# Circuit_diagram_source_file.net
KiCad netlist of a schematic drawn in Altium Designer
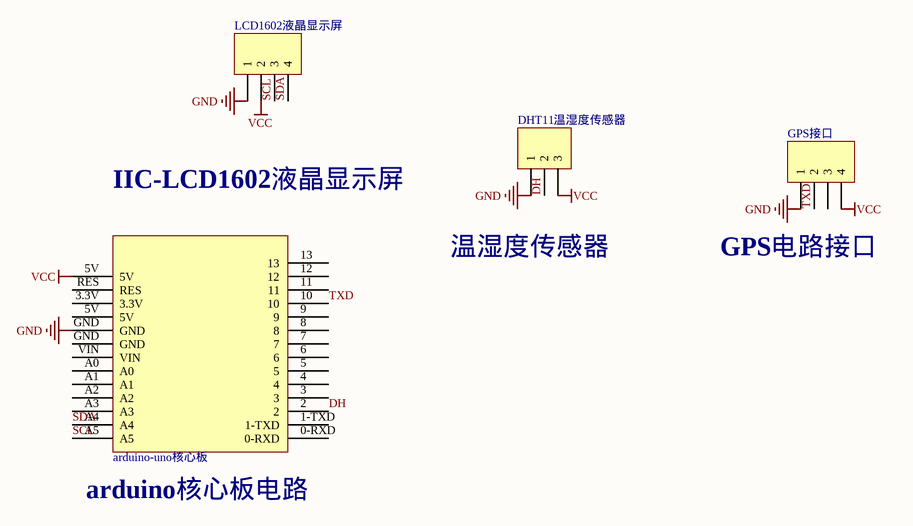
[diagram p0: Circuit diagram source file.SchDoc]

(export (version "E")
  (design (tool "Eeschema 10.0.6"))
  (components
    (comp (ref "arduino-uno核心板") (value "Component_2") (libsource (lib "Schlib1") (part "Component_2")))
    (comp (ref "DHT11温湿度传感器")
      (value "Header 3")
      (footprint "HDR1X3")
      (description "Header, 3-Pin")
      (fields (field (name "PUBLISHER") "Altium Limited"))
      (libsource (lib "Miscellaneous Connectors") (part "Header 3"))
    )
    (comp (ref "GPS接口")
      (value "Header 4")
      (footprint "HDR1X4")
      (description "Header, 4-Pin")
      (fields (field (name "PUBLISHER") "Altium Limited"))
      (libsource (lib "Miscellaneous Connectors") (part "Header 4"))
    )
    (comp (ref "LCD1602液晶显示屏")
      (value "Header 4")
      (footprint "HDR1X4")
      (description "Header, 4-Pin")
      (fields (field (name "PUBLISHER") "Altium Limited"))
      (libsource (lib "Miscellaneous Connectors") (part "Header 4"))
    )
  )
  (nets
    (net (code "1") (name "/DH") (class "Default")
      (node (ref "DHT11温湿度传感器") (pin "2") (pinfunction "2_2") (pintype "passive"))
      (node (ref "arduino-uno核心板") (pin "2") (pinfunction "2_2") (pintype "passive"))
    )
    (net (code "2") (name "/SCL") (class "Default")
      (node (ref "LCD1602液晶显示屏") (pin "3") (pinfunction "3_3") (pintype "passive"))
      (node (ref "arduino-uno核心板") (pin "A5") (pinfunction "A5_A5") (pintype "passive"))
    )
    (net (code "3") (name "/SDA") (class "Default")
      (node (ref "LCD1602液晶显示屏") (pin "4") (pinfunction "4_4") (pintype "passive"))
      (node (ref "arduino-uno核心板") (pin "A4") (pinfunction "A4_A4") (pintype "passive"))
    )
    (net (code "4") (name "/TXD") (class "Default")
      (node (ref "GPS接口") (pin "2") (pinfunction "2_2") (pintype "passive"))
      (node (ref "arduino-uno核心板") (pin "10") (pinfunction "10_10") (pintype "passive"))
    )
    (net (code "5") (name "GND") (class "Default")
      (node (ref "DHT11温湿度传感器") (pin "1") (pinfunction "1_1") (pintype "passive"))
      (node (ref "GPS接口") (pin "1") (pinfunction "1_1") (pintype "passive"))
      (node (ref "LCD1602液晶显示屏") (pin "1") (pinfunction "1_1") (pintype "passive"))
      (node (ref "arduino-uno核心板") (pin "GND") (pinfunction "GND_GND") (pintype "passive"))
    )
    (net (code "6") (name "VCC") (class "Default")
      (node (ref "DHT11温湿度传感器") (pin "3") (pinfunction "3_3") (pintype "passive"))
      (node (ref "GPS接口") (pin "4") (pinfunction "4_4") (pintype "passive"))
      (node (ref "LCD1602液晶显示屏") (pin "2") (pinfunction "2_2") (pintype "passive"))
      (node (ref "arduino-uno核心板") (pin "5V") (pinfunction "5V_5V") (pintype "passive"))
    )
    (net (code "7") (name "unconnected-(GPS接口-Pad3)") (class "Default")
      (node (ref "GPS接口") (pin "3") (pinfunction "3_3") (pintype "passive"))
    )
    (net (code "8") (name "unconnected-(arduino-uno核心板-Pad0-RXD)") (class "Default")
      (node (ref "arduino-uno核心板") (pin "0-RXD") (pinfunction "0-RXD_0-RXD") (pintype "passive"))
    )
    (net (code "9") (name "unconnected-(arduino-uno核心板-Pad1-TXD)") (class "Default")
      (node (ref "arduino-uno核心板") (pin "1-TXD") (pinfunction "1-TXD_1-TXD") (pintype "passive"))
    )
    (net (code "10") (name "unconnected-(arduino-uno核心板-Pad3)") (class "Default")
      (node (ref "arduino-uno核心板") (pin "3") (pinfunction "3_3") (pintype "passive"))
    )
    (net (code "11") (name "unconnected-(arduino-uno核心板-Pad3.3V)") (class "Default")
      (node (ref "arduino-uno核心板") (pin "3.3V") (pinfunction "3.3V_3.3V") (pintype "passive"))
    )
    (net (code "12") (name "unconnected-(arduino-uno核心板-Pad4)") (class "Default")
      (node (ref "arduino-uno核心板") (pin "4") (pinfunction "4_4") (pintype "passive"))
    )
    (net (code "13") (name "unconnected-(arduino-uno核心板-Pad5)") (class "Default")
      (node (ref "arduino-uno核心板") (pin "5") (pinfunction "5_5") (pintype "passive"))
    )
    (net (code "14") (name "unconnected-(arduino-uno核心板-Pad5V)") (class "Default")
      (node (ref "arduino-uno核心板") (pin "5V") (pinfunction "5V_5V") (pintype "passive"))
    )
    (net (code "15") (name "unconnected-(arduino-uno核心板-Pad6)") (class "Default")
      (node (ref "arduino-uno核心板") (pin "6") (pinfunction "6_6") (pintype "passive"))
    )
    (net (code "16") (name "unconnected-(arduino-uno核心板-Pad7)") (class "Default")
      (node (ref "arduino-uno核心板") (pin "7") (pinfunction "7_7") (pintype "passive"))
    )
    (net (code "17") (name "unconnected-(arduino-uno核心板-Pad8)") (class "Default")
      (node (ref "arduino-uno核心板") (pin "8") (pinfunction "8_8") (pintype "passive"))
    )
    (net (code "18") (name "unconnected-(arduino-uno核心板-Pad9)") (class "Default")
      (node (ref "arduino-uno核心板") (pin "9") (pinfunction "9_9") (pintype "passive"))
    )
    (net (code "19") (name "unconnected-(arduino-uno核心板-Pad11)") (class "Default")
      (node (ref "arduino-uno核心板") (pin "11") (pinfunction "11_11") (pintype "passive"))
    )
    (net (code "20") (name "unconnected-(arduino-uno核心板-Pad12)") (class "Default")
      (node (ref "arduino-uno核心板") (pin "12") (pinfunction "12_12") (pintype "passive"))
    )
    (net (code "21") (name "unconnected-(arduino-uno核心板-Pad13)") (class "Default")
      (node (ref "arduino-uno核心板") (pin "13") (pinfunction "13_13") (pintype "passive"))
    )
    (net (code "22") (name "unconnected-(arduino-uno核心板-PadA0)") (class "Default")
      (node (ref "arduino-uno核心板") (pin "A0") (pinfunction "A0_A0") (pintype "passive"))
    )
    (net (code "23") (name "unconnected-(arduino-uno核心板-PadA1)") (class "Default")
      (node (ref "arduino-uno核心板") (pin "A1") (pinfunction "A1_A1") (pintype "passive"))
    )
    (net (code "24") (name "unconnected-(arduino-uno核心板-PadA2)") (class "Default")
      (node (ref "arduino-uno核心板") (pin "A2") (pinfunction "A2_A2") (pintype "passive"))
    )
    (net (code "25") (name "unconnected-(arduino-uno核心板-PadA3)") (class "Default")
      (node (ref "arduino-uno核心板") (pin "A3") (pinfunction "A3_A3") (pintype "passive"))
    )
    (net (code "26") (name "unconnected-(arduino-uno核心板-PadGND)") (class "Default")
      (node (ref "arduino-uno核心板") (pin "GND") (pinfunction "GND_GND") (pintype "passive"))
    )
    (net (code "27") (name "unconnected-(arduino-uno核心板-PadRES)") (class "Default")
      (node (ref "arduino-uno核心板") (pin "RES") (pinfunction "RES_RES") (pintype "passive"))
    )
    (net (code "28") (name "unconnected-(arduino-uno核心板-PadVIN)") (class "Default")
      (node (ref "arduino-uno核心板") (pin "VIN") (pinfunction "VIN_VIN") (pintype "passive"))
    )
  )
)
